# BoardB-FPGA2.net
KiCad netlist of a schematic drawn in Altium Designer
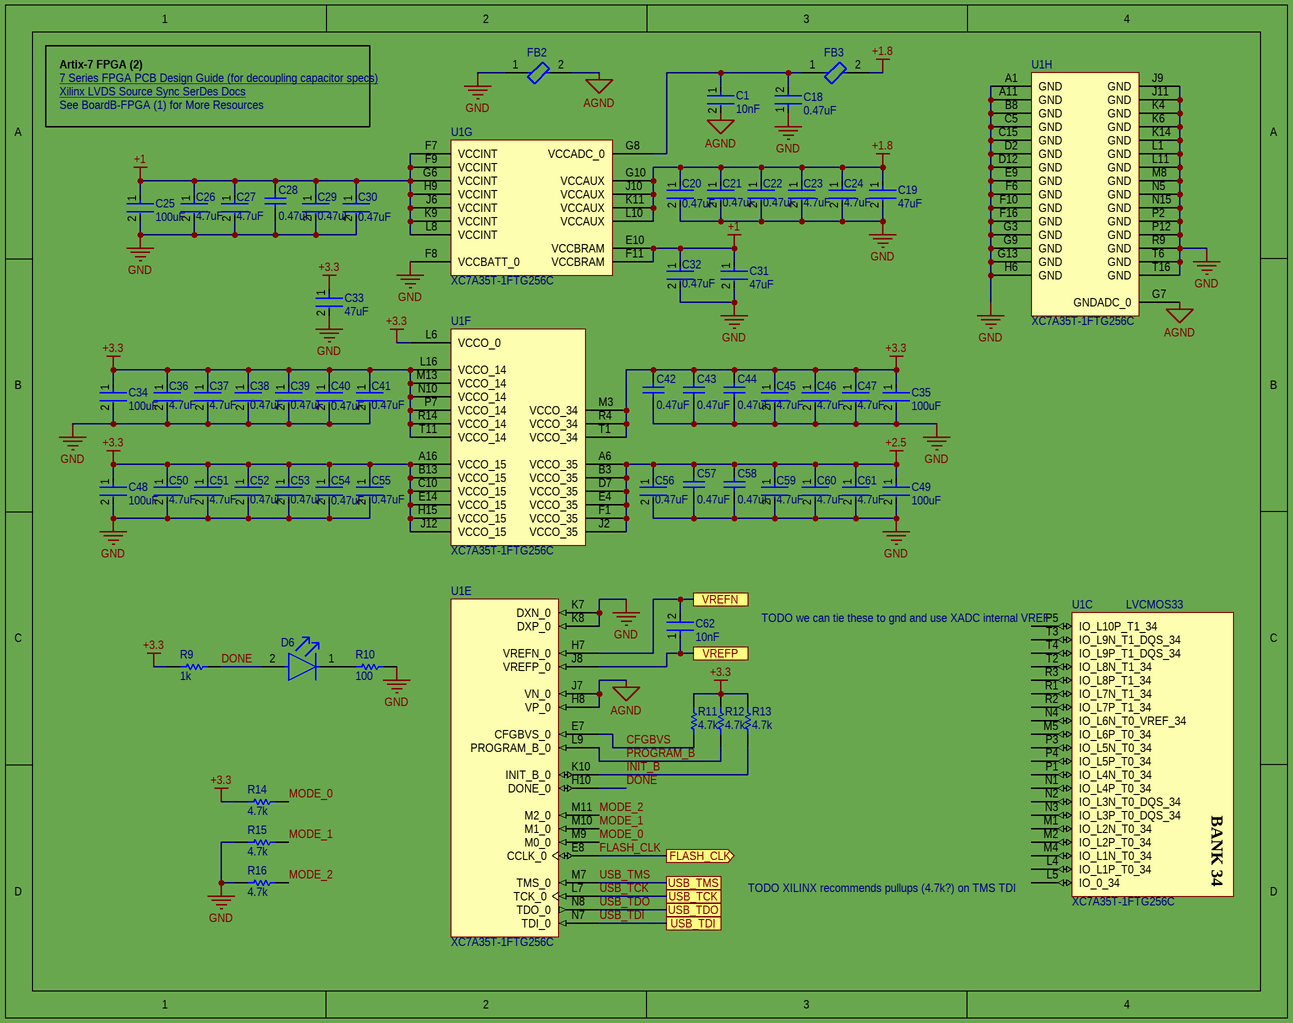
[diagram p0: BoardB-FPGA2.SchDoc]

(export (version "E")
  (design (tool "Eeschema 10.0.6"))
  (components
    (comp (ref "C1")
      (value "10nF")
      (footprint "FP-GRM033-0_03-IPC_C")
      (description "Chip Multilayer Ceramic Capacitors for General Purpose, 0201, 10000pF, X7R, 15%, 10%, 10V")
      (fields (field (name "VOLTAGE") "10V") (field (name "TOLERANCE") "10%"))
      (libsource (lib "Altium Content Vault") (part "b4654b650e69147ec39a6b967a45e02"))
    )
    (comp (ref "C18")
      (value "0.47uF")
      (footprint "FP-GRM033-0_03-IPC_C")
      (description "Chip Multilayer Ceramic Capacitors for General Purpose, 0201, 0.47uF, X5R, 15%, 10%, 6.3V")
      (fields (field (name "TOLERANCE") "10%"))
      (libsource (lib "Altium Content Vault") (part "b4654b650e69147ec39a6b967a45e02"))
    )
    (comp (ref "C19")
      (value "47uF")
      (footprint "FP-GRM188-0_2-MFG")
      (description "Chip Multilayer Ceramic Capacitors for General Purpose, 0603, 47uF, X5R, 15%, 20%, 6.3V")
      (fields (field (name "TOLERANCE") "20%"))
      (libsource (lib "Altium Content Vault") (part "11868f565c42a9108669ba33697ecf6"))
    )
    (comp (ref "C20")
      (value "0.47uF")
      (footprint "FP-GRM033-0_03-IPC_C")
      (description "Chip Multilayer Ceramic Capacitors for General Purpose, 0201, 0.47uF, X5R, 15%, 10%, 6.3V")
      (fields (field (name "TOLERANCE") "10%"))
      (libsource (lib "Altium Content Vault") (part "b4654b650e69147ec39a6b967a45e02"))
    )
    (comp (ref "C21")
      (value "0.47uF")
      (footprint "FP-GRM033-0_03-IPC_C")
      (description "Chip Multilayer Ceramic Capacitors for General Purpose, 0201, 0.47uF, X5R, 15%, 10%, 6.3V")
      (fields (field (name "TOLERANCE") "10%"))
      (libsource (lib "Altium Content Vault") (part "b4654b650e69147ec39a6b967a45e02"))
    )
    (comp (ref "C22")
      (value "0.47uF")
      (footprint "FP-GRM033-0_03-IPC_C")
      (description "Chip Multilayer Ceramic Capacitors for General Purpose, 0201, 0.47uF, X5R, 15%, 10%, 6.3V")
      (fields (field (name "TOLERANCE") "10%"))
      (libsource (lib "Altium Content Vault") (part "b4654b650e69147ec39a6b967a45e02"))
    )
    (comp (ref "C23")
      (value "4.7uF")
      (footprint "FP-GRM155-0_1-IPC_B")
      (description "Chip Multilayer Ceramic Capacitors for General Purpose, 0402, 4.7uF, X5R, 15%, 20%, 6.3V")
      (fields (field (name "VOLTAGE") "6.3V") (field (name "TOLERANCE") "20%"))
      (libsource (lib "Altium Content Vault") (part "11868f565c42a9108669ba33697ecf6"))
    )
    (comp (ref "C24")
      (value "4.7uF")
      (footprint "FP-GRM155-0_1-IPC_B")
      (description "Chip Multilayer Ceramic Capacitors for General Purpose, 0402, 4.7uF, X5R, 15%, 20%, 6.3V")
      (fields (field (name "VOLTAGE") "6.3V") (field (name "TOLERANCE") "20%"))
      (libsource (lib "Altium Content Vault") (part "11868f565c42a9108669ba33697ecf6"))
    )
    (comp (ref "C25")
      (value "100uF")
      (footprint "FP-GRM21B-0_2-e0_2_0_7-MFG")
      (description "Chip Multilayer Ceramic Capacitors for General Purpose, 0805, 100uF, X5R, 15%, 20%, 6.3V")
      (fields (field (name "TOLERANCE") "20%"))
      (libsource (lib "Altium Content Vault") (part "b4654b650e69147ec39a6b967a45e02"))
    )
    (comp (ref "C26")
      (value "4.7uF")
      (footprint "FP-GRM155-0_1-IPC_B")
      (description "Chip Multilayer Ceramic Capacitors for General Purpose, 0402, 4.7uF, X5R, 15%, 20%, 6.3V")
      (fields (field (name "VOLTAGE") "6.3V") (field (name "TOLERANCE") "20%"))
      (libsource (lib "Altium Content Vault") (part "11868f565c42a9108669ba33697ecf6"))
    )
    (comp (ref "C27")
      (value "4.7uF")
      (footprint "FP-GRM155-0_1-IPC_B")
      (description "Chip Multilayer Ceramic Capacitors for General Purpose, 0402, 4.7uF, X5R, 15%, 20%, 6.3V")
      (fields (field (name "VOLTAGE") "6.3V") (field (name "TOLERANCE") "20%"))
      (libsource (lib "Altium Content Vault") (part "11868f565c42a9108669ba33697ecf6"))
    )
    (comp (ref "C28")
      (value "0.47uF")
      (footprint "CAPC1005X55X25LL05T10")
      (fields (field (name "MANUFACTURER") "Murata") (field (name "PART NUMBER") "GRM155R60J474KE19D"))
      (libsource (lib "Altium Content Vault") (part "CAP"))
    )
    (comp (ref "C29")
      (value "0.47uF")
      (footprint "FP-GRM033-0_03-IPC_C")
      (description "Chip Multilayer Ceramic Capacitors for General Purpose, 0201, 0.47uF, X5R, 15%, 10%, 6.3V")
      (fields (field (name "TOLERANCE") "10%"))
      (libsource (lib "Altium Content Vault") (part "b4654b650e69147ec39a6b967a45e02"))
    )
    (comp (ref "C30")
      (value "0.47uF")
      (footprint "FP-GRM033-0_03-IPC_C")
      (description "Chip Multilayer Ceramic Capacitors for General Purpose, 0201, 0.47uF, X5R, 15%, 10%, 6.3V")
      (fields (field (name "TOLERANCE") "10%"))
      (libsource (lib "Altium Content Vault") (part "b4654b650e69147ec39a6b967a45e02"))
    )
    (comp (ref "C31")
      (value "47uF")
      (footprint "FP-GRM188-0_2-MFG")
      (description "Chip Multilayer Ceramic Capacitors for General Purpose, 0603, 47uF, X5R, 15%, 20%, 6.3V")
      (fields (field (name "TOLERANCE") "20%"))
      (libsource (lib "Altium Content Vault") (part "11868f565c42a9108669ba33697ecf6"))
    )
    (comp (ref "C32")
      (value "0.47uF")
      (footprint "FP-GRM033-0_03-IPC_C")
      (description "Chip Multilayer Ceramic Capacitors for General Purpose, 0201, 0.47uF, X5R, 15%, 10%, 6.3V")
      (fields (field (name "TOLERANCE") "10%"))
      (libsource (lib "Altium Content Vault") (part "b4654b650e69147ec39a6b967a45e02"))
    )
    (comp (ref "C33")
      (value "47uF")
      (footprint "FP-GRM188-0_2-MFG")
      (description "Chip Multilayer Ceramic Capacitors for General Purpose, 0603, 47uF, X5R, 15%, 20%, 6.3V")
      (fields (field (name "TOLERANCE") "20%"))
      (libsource (lib "Altium Content Vault") (part "11868f565c42a9108669ba33697ecf6"))
    )
    (comp (ref "C34")
      (value "100uF")
      (footprint "FP-GRM21B-0_2-e0_2_0_7-MFG")
      (description "Chip Multilayer Ceramic Capacitors for General Purpose, 0805, 100uF, X5R, 15%, 20%, 6.3V")
      (fields (field (name "TOLERANCE") "20%"))
      (libsource (lib "Altium Content Vault") (part "b4654b650e69147ec39a6b967a45e02"))
    )
    (comp (ref "C35")
      (value "100uF")
      (footprint "FP-GRM21B-0_2-e0_2_0_7-MFG")
      (description "Chip Multilayer Ceramic Capacitors for General Purpose, 0805, 100uF, X5R, 15%, 20%, 6.3V")
      (fields (field (name "TOLERANCE") "20%"))
      (libsource (lib "Altium Content Vault") (part "b4654b650e69147ec39a6b967a45e02"))
    )
    (comp (ref "C36")
      (value "4.7uF")
      (footprint "FP-GRM155-0_1-IPC_B")
      (description "Chip Multilayer Ceramic Capacitors for General Purpose, 0402, 4.7uF, X5R, 15%, 20%, 6.3V")
      (fields (field (name "VOLTAGE") "6.3V") (field (name "TOLERANCE") "20%"))
      (libsource (lib "Altium Content Vault") (part "11868f565c42a9108669ba33697ecf6"))
    )
    (comp (ref "C37")
      (value "4.7uF")
      (footprint "FP-GRM155-0_1-IPC_B")
      (description "Chip Multilayer Ceramic Capacitors for General Purpose, 0402, 4.7uF, X5R, 15%, 20%, 6.3V")
      (fields (field (name "VOLTAGE") "6.3V") (field (name "TOLERANCE") "20%"))
      (libsource (lib "Altium Content Vault") (part "11868f565c42a9108669ba33697ecf6"))
    )
    (comp (ref "C38")
      (value "0.47uF")
      (footprint "FP-GRM033-0_03-IPC_C")
      (description "Chip Multilayer Ceramic Capacitors for General Purpose, 0201, 0.47uF, X5R, 15%, 10%, 6.3V")
      (fields (field (name "TOLERANCE") "10%"))
      (libsource (lib "Altium Content Vault") (part "b4654b650e69147ec39a6b967a45e02"))
    )
    (comp (ref "C39")
      (value "0.47uF")
      (footprint "FP-GRM033-0_03-IPC_C")
      (description "Chip Multilayer Ceramic Capacitors for General Purpose, 0201, 0.47uF, X5R, 15%, 10%, 6.3V")
      (fields (field (name "TOLERANCE") "10%"))
      (libsource (lib "Altium Content Vault") (part "b4654b650e69147ec39a6b967a45e02"))
    )
    (comp (ref "C40")
      (value "0.47uF")
      (footprint "FP-GRM033-0_03-IPC_C")
      (description "Chip Multilayer Ceramic Capacitors for General Purpose, 0201, 0.47uF, X5R, 15%, 10%, 6.3V")
      (fields (field (name "TOLERANCE") "10%"))
      (libsource (lib "Altium Content Vault") (part "b4654b650e69147ec39a6b967a45e02"))
    )
    (comp (ref "C41")
      (value "0.47uF")
      (footprint "FP-GRM033-0_03-IPC_C")
      (description "Chip Multilayer Ceramic Capacitors for General Purpose, 0201, 0.47uF, X5R, 15%, 10%, 6.3V")
      (fields (field (name "TOLERANCE") "10%"))
      (libsource (lib "Altium Content Vault") (part "b4654b650e69147ec39a6b967a45e02"))
    )
    (comp (ref "C42")
      (value "0.47uF")
      (footprint "CAPC1005X55X25LL05T10")
      (fields (field (name "MANUFACTURER") "Murata") (field (name "PART NUMBER") "GRM155R60J474KE19D"))
      (libsource (lib "Altium Content Vault") (part "CAP"))
    )
    (comp (ref "C43")
      (value "0.47uF")
      (footprint "CAPC1005X55X25LL05T10")
      (fields (field (name "MANUFACTURER") "Murata") (field (name "PART NUMBER") "GRM155R60J474KE19D"))
      (libsource (lib "Altium Content Vault") (part "CAP"))
    )
    (comp (ref "C44")
      (value "0.47uF")
      (footprint "CAPC1005X55X25LL05T10")
      (fields (field (name "MANUFACTURER") "Murata") (field (name "PART NUMBER") "GRM155R60J474KE19D"))
      (libsource (lib "Altium Content Vault") (part "CAP"))
    )
    (comp (ref "C45")
      (value "4.7uF")
      (footprint "FP-GRM155-0_1-IPC_B")
      (description "Chip Multilayer Ceramic Capacitors for General Purpose, 0402, 4.7uF, X5R, 15%, 20%, 6.3V")
      (fields (field (name "VOLTAGE") "6.3V") (field (name "TOLERANCE") "20%"))
      (libsource (lib "Altium Content Vault") (part "11868f565c42a9108669ba33697ecf6"))
    )
    (comp (ref "C46")
      (value "4.7uF")
      (footprint "FP-GRM155-0_1-IPC_B")
      (description "Chip Multilayer Ceramic Capacitors for General Purpose, 0402, 4.7uF, X5R, 15%, 20%, 6.3V")
      (fields (field (name "VOLTAGE") "6.3V") (field (name "TOLERANCE") "20%"))
      (libsource (lib "Altium Content Vault") (part "11868f565c42a9108669ba33697ecf6"))
    )
    (comp (ref "C47")
      (value "4.7uF")
      (footprint "FP-GRM155-0_1-IPC_B")
      (description "Chip Multilayer Ceramic Capacitors for General Purpose, 0402, 4.7uF, X5R, 15%, 20%, 6.3V")
      (fields (field (name "VOLTAGE") "6.3V") (field (name "TOLERANCE") "20%"))
      (libsource (lib "Altium Content Vault") (part "11868f565c42a9108669ba33697ecf6"))
    )
    (comp (ref "C48")
      (value "100uF")
      (footprint "FP-GRM21B-0_2-e0_2_0_7-MFG")
      (description "Chip Multilayer Ceramic Capacitors for General Purpose, 0805, 100uF, X5R, 15%, 20%, 6.3V")
      (fields (field (name "TOLERANCE") "20%"))
      (libsource (lib "Altium Content Vault") (part "b4654b650e69147ec39a6b967a45e02"))
    )
    (comp (ref "C49")
      (value "100uF")
      (footprint "FP-GRM21B-0_2-e0_2_0_7-MFG")
      (description "Chip Multilayer Ceramic Capacitors for General Purpose, 0805, 100uF, X5R, 15%, 20%, 6.3V")
      (fields (field (name "TOLERANCE") "20%"))
      (libsource (lib "Altium Content Vault") (part "b4654b650e69147ec39a6b967a45e02"))
    )
    (comp (ref "C50")
      (value "4.7uF")
      (footprint "FP-GRM155-0_1-IPC_B")
      (description "Chip Multilayer Ceramic Capacitors for General Purpose, 0402, 4.7uF, X5R, 15%, 20%, 6.3V")
      (fields (field (name "VOLTAGE") "6.3V") (field (name "TOLERANCE") "20%"))
      (libsource (lib "Altium Content Vault") (part "11868f565c42a9108669ba33697ecf6"))
    )
    (comp (ref "C51")
      (value "4.7uF")
      (footprint "FP-GRM155-0_1-IPC_B")
      (description "Chip Multilayer Ceramic Capacitors for General Purpose, 0402, 4.7uF, X5R, 15%, 20%, 6.3V")
      (fields (field (name "VOLTAGE") "6.3V") (field (name "TOLERANCE") "20%"))
      (libsource (lib "Altium Content Vault") (part "11868f565c42a9108669ba33697ecf6"))
    )
    (comp (ref "C52")
      (value "0.47uF")
      (footprint "FP-GRM033-0_03-IPC_C")
      (description "Chip Multilayer Ceramic Capacitors for General Purpose, 0201, 0.47uF, X5R, 15%, 10%, 6.3V")
      (fields (field (name "TOLERANCE") "10%"))
      (libsource (lib "Altium Content Vault") (part "b4654b650e69147ec39a6b967a45e02"))
    )
    (comp (ref "C53")
      (value "0.47uF")
      (footprint "FP-GRM033-0_03-IPC_C")
      (description "Chip Multilayer Ceramic Capacitors for General Purpose, 0201, 0.47uF, X5R, 15%, 10%, 6.3V")
      (fields (field (name "TOLERANCE") "10%"))
      (libsource (lib "Altium Content Vault") (part "b4654b650e69147ec39a6b967a45e02"))
    )
    (comp (ref "C54")
      (value "0.47uF")
      (footprint "FP-GRM033-0_03-IPC_C")
      (description "Chip Multilayer Ceramic Capacitors for General Purpose, 0201, 0.47uF, X5R, 15%, 10%, 6.3V")
      (fields (field (name "TOLERANCE") "10%"))
      (libsource (lib "Altium Content Vault") (part "b4654b650e69147ec39a6b967a45e02"))
    )
    (comp (ref "C55")
      (value "0.47uF")
      (footprint "FP-GRM033-0_03-IPC_C")
      (description "Chip Multilayer Ceramic Capacitors for General Purpose, 0201, 0.47uF, X5R, 15%, 10%, 6.3V")
      (fields (field (name "TOLERANCE") "10%"))
      (libsource (lib "Altium Content Vault") (part "b4654b650e69147ec39a6b967a45e02"))
    )
    (comp (ref "C56")
      (value "0.47uF")
      (footprint "FP-GRM033-0_03-IPC_C")
      (description "Chip Multilayer Ceramic Capacitors for General Purpose, 0201, 0.47uF, X5R, 15%, 10%, 6.3V")
      (fields (field (name "TOLERANCE") "10%"))
      (libsource (lib "Altium Content Vault") (part "b4654b650e69147ec39a6b967a45e02"))
    )
    (comp (ref "C57")
      (value "0.47uF")
      (footprint "CAPC1005X55X25LL05T10")
      (fields (field (name "MANUFACTURER") "Murata") (field (name "PART NUMBER") "GRM155R60J474KE19D"))
      (libsource (lib "Altium Content Vault") (part "CAP"))
    )
    (comp (ref "C58")
      (value "0.47uF")
      (footprint "CAPC1005X55X25LL05T10")
      (fields (field (name "MANUFACTURER") "Murata") (field (name "PART NUMBER") "GRM155R60J474KE19D"))
      (libsource (lib "Altium Content Vault") (part "CAP"))
    )
    (comp (ref "C59")
      (value "4.7uF")
      (footprint "FP-GRM155-0_1-IPC_B")
      (description "Chip Multilayer Ceramic Capacitors for General Purpose, 0402, 4.7uF, X5R, 15%, 20%, 6.3V")
      (fields (field (name "VOLTAGE") "6.3V") (field (name "TOLERANCE") "20%"))
      (libsource (lib "Altium Content Vault") (part "11868f565c42a9108669ba33697ecf6"))
    )
    (comp (ref "C60")
      (value "4.7uF")
      (footprint "FP-GRM155-0_1-IPC_B")
      (description "Chip Multilayer Ceramic Capacitors for General Purpose, 0402, 4.7uF, X5R, 15%, 20%, 6.3V")
      (fields (field (name "VOLTAGE") "6.3V") (field (name "TOLERANCE") "20%"))
      (libsource (lib "Altium Content Vault") (part "11868f565c42a9108669ba33697ecf6"))
    )
    (comp (ref "C61")
      (value "4.7uF")
      (footprint "FP-GRM155-0_1-IPC_B")
      (description "Chip Multilayer Ceramic Capacitors for General Purpose, 0402, 4.7uF, X5R, 15%, 20%, 6.3V")
      (fields (field (name "VOLTAGE") "6.3V") (field (name "TOLERANCE") "20%"))
      (libsource (lib "Altium Content Vault") (part "11868f565c42a9108669ba33697ecf6"))
    )
    (comp (ref "C62")
      (value "10nF")
      (footprint "FP-CC0201-BA-MFG")
      (description "CAP CER 10000PF 16V X7R 0201")
      (fields
        (field (name "OCTOPART") "https://octopart.com/cc0201krx7r7bb103-yageo-9292627")
        (field (name "MANUFACTURER") "Yageo")
      )
      (libsource (lib "Altium Content Vault") (part "11868f565c42a9108669ba33697ecf6"))
    )
    (comp (ref "D6")
      (value "SML-D12U1WT86")
      (footprint "FP-SML-D12-MFG")
      (description "LED RED DIFFUSED 1608 SMD")
      (fields
        (field (name "MANUFACTURER") "Rohm")
        (field (name "OCTOPART") "https://octopart.com/sml-d12u1wt86-rohm-70850259")
      )
      (libsource (lib "Altium Content Vault") (part "8706943c75ba83719d021d2fdc84c58"))
    )
    (comp (ref "FB2")
      (value "BLM18AG601SN1D")
      (footprint "FP-BLM18-0_15-t0_8-MFG")
      (description "Chip Ferrite Bead, 0603, 600Ω @ 100MHz, 0.38Ω, 25%, 500mA")
      (fields (field (name "TOLERANCE") "25%"))
      (libsource (lib "Altium Content Vault") (part "5f30dd21d616792df468990f7003faa"))
    )
    (comp (ref "FB3")
      (value "BLM18AG601SN1D")
      (footprint "FP-BLM18-0_15-t0_8-MFG")
      (description "Chip Ferrite Bead, 0603, 600Ω @ 100MHz, 0.38Ω, 25%, 500mA")
      (fields (field (name "TOLERANCE") "25%"))
      (libsource (lib "Altium Content Vault") (part "5f30dd21d616792df468990f7003faa"))
    )
    (comp (ref "R9")
      (value "1k")
      (footprint "RESC1005X40X25NL05T05")
      (description "Chip Resistor, 1 KOhm, +/- 1%, 100 mW, -55 to 155 degC, 0402 (1005 Metric), RoHS, Tape and Reel")
      (fields (field (name "PARTNUMBER") "ERJ-2RKF1001X") (field (name "MANUFACTURER") "Basic Passives"))
      (libsource (lib "Altium Content Vault") (part "RES-2"))
    )
    (comp (ref "R10")
      (value "100")
      (footprint "RESC1005X40X25LL05T05")
      (description "Chip Resistor, 100 Ohm, +/- 1%, 100 mW, -55 to 155 degC, 0402 (1005 Metric), RoHS, Tape and Reel")
      (fields (field (name "MANUFACTURER") "Basic Passives") (field (name "TOLERANCE") "1%"))
      (libsource (lib "Altium Content Vault") (part "RES-2"))
    )
    (comp (ref "R11")
      (value "4.7k")
      (footprint "RESC1005X40X25LL05T05")
      (description "Chip Resistor, 4.7 KOhm, +/- 1%, 0.1 W, -55 to 155 degC, 0402 (1005 Metric), RoHS, Tape and Reel")
      (fields (field (name "TOLERANCE") "1%") (field (name "PARTNUMBER") "ERJ-2RKF4701X"))
      (libsource (lib "Altium Content Vault") (part "RES-2"))
    )
    (comp (ref "R12")
      (value "4.7k")
      (footprint "RESC1005X40X25LL05T05")
      (description "Chip Resistor, 4.7 KOhm, +/- 1%, 0.1 W, -55 to 155 degC, 0402 (1005 Metric), RoHS, Tape and Reel")
      (fields (field (name "TOLERANCE") "1%") (field (name "PARTNUMBER") "ERJ-2RKF4701X"))
      (libsource (lib "Altium Content Vault") (part "RES-2"))
    )
    (comp (ref "R13")
      (value "4.7k")
      (footprint "RESC1005X40X25LL05T05")
      (description "Chip Resistor, 4.7 KOhm, +/- 1%, 0.1 W, -55 to 155 degC, 0402 (1005 Metric), RoHS, Tape and Reel")
      (fields (field (name "TOLERANCE") "1%") (field (name "PARTNUMBER") "ERJ-2RKF4701X"))
      (libsource (lib "Altium Content Vault") (part "RES-2"))
    )
    (comp (ref "R14")
      (value "4.7k")
      (footprint "RESC1005X40X25LL05T05")
      (description "Chip Resistor, 4.7 KOhm, +/- 1%, 0.1 W, -55 to 155 degC, 0402 (1005 Metric), RoHS, Tape and Reel")
      (fields (field (name "TOLERANCE") "1%") (field (name "PARTNUMBER") "ERJ-2RKF4701X"))
      (libsource (lib "Altium Content Vault") (part "RES-2"))
    )
    (comp (ref "R15")
      (value "4.7k")
      (footprint "RESC1005X40X25LL05T05")
      (description "Chip Resistor, 4.7 KOhm, +/- 1%, 0.1 W, -55 to 155 degC, 0402 (1005 Metric), RoHS, Tape and Reel")
      (fields (field (name "TOLERANCE") "1%") (field (name "PARTNUMBER") "ERJ-2RKF4701X"))
      (libsource (lib "Altium Content Vault") (part "RES-2"))
    )
    (comp (ref "R16")
      (value "4.7k")
      (footprint "RESC1005X40X25LL05T05")
      (description "Chip Resistor, 4.7 KOhm, +/- 1%, 0.1 W, -55 to 155 degC, 0402 (1005 Metric), RoHS, Tape and Reel")
      (fields (field (name "TOLERANCE") "1%") (field (name "PARTNUMBER") "ERJ-2RKF4701X"))
      (libsource (lib "Altium Content Vault") (part "RES-2"))
    )
    (comp (ref "U1")
      (value "XC7A35T-1FTG256C")
      (footprint "FTG256")
      (description "Artix-7 FPGA, 170 User I/Os, 0 GTP, 256-Ball BGA, Speed Grade 1, Commercial Grade, Pb-Free")
      (fields (field (name "MANUFACTURER") "Xilinx"))
      (libsource (lib "Altium Content Vault") (part "XLNX-XC7A35T-FTG256"))
    )
  )
  (nets
    (net (code "1") (name "+1") (class "Default")
      (node (ref "C25") (pin "1") (pinfunction "1_1") (pintype "passive"))
      (node (ref "C26") (pin "1") (pinfunction "1_1") (pintype "passive"))
      (node (ref "C27") (pin "1") (pinfunction "1_1") (pintype "passive"))
      (node (ref "C28") (pin "2") (pinfunction "2_2") (pintype "passive"))
      (node (ref "C29") (pin "1") (pinfunction "1_1") (pintype "passive"))
      (node (ref "C30") (pin "1") (pinfunction "1_1") (pintype "passive"))
      (node (ref "C31") (pin "1") (pinfunction "1_1") (pintype "passive"))
      (node (ref "C32") (pin "1") (pinfunction "1_1") (pintype "passive"))
      (node (ref "U1") (pin "E10") (pinfunction "VCCBRAM_E10") (pintype "power_in"))
      (node (ref "U1") (pin "F11") (pinfunction "VCCBRAM_F11") (pintype "power_in"))
      (node (ref "U1") (pin "F7") (pinfunction "VCCINT_F7") (pintype "power_in"))
      (node (ref "U1") (pin "F9") (pinfunction "VCCINT_F9") (pintype "power_in"))
      (node (ref "U1") (pin "G6") (pinfunction "VCCINT_G6") (pintype "power_in"))
      (node (ref "U1") (pin "H9") (pinfunction "VCCINT_H9") (pintype "power_in"))
      (node (ref "U1") (pin "J6") (pinfunction "VCCINT_J6") (pintype "power_in"))
      (node (ref "U1") (pin "K9") (pinfunction "VCCINT_K9") (pintype "power_in"))
      (node (ref "U1") (pin "L8") (pinfunction "VCCINT_L8") (pintype "power_in"))
    )
    (net (code "2") (name "+1.8") (class "Default")
      (node (ref "C19") (pin "1") (pinfunction "1_1") (pintype "passive"))
      (node (ref "C20") (pin "1") (pinfunction "1_1") (pintype "passive"))
      (node (ref "C21") (pin "1") (pinfunction "1_1") (pintype "passive"))
      (node (ref "C22") (pin "1") (pinfunction "1_1") (pintype "passive"))
      (node (ref "C23") (pin "1") (pinfunction "1_1") (pintype "passive"))
      (node (ref "C24") (pin "1") (pinfunction "1_1") (pintype "passive"))
      (node (ref "FB3") (pin "2") (pinfunction "2_2") (pintype "passive"))
      (node (ref "U1") (pin "G10") (pinfunction "VCCAUX_G10") (pintype "power_in"))
      (node (ref "U1") (pin "J10") (pinfunction "VCCAUX_J10") (pintype "power_in"))
      (node (ref "U1") (pin "K11") (pinfunction "VCCAUX_K11") (pintype "power_in"))
      (node (ref "U1") (pin "L10") (pinfunction "VCCAUX_L10") (pintype "power_in"))
    )
    (net (code "3") (name "+2.5") (class "Default")
      (node (ref "C49") (pin "1") (pinfunction "1_1") (pintype "passive"))
      (node (ref "C56") (pin "1") (pinfunction "1_1") (pintype "passive"))
      (node (ref "C57") (pin "2") (pinfunction "2_2") (pintype "passive"))
      (node (ref "C58") (pin "2") (pinfunction "2_2") (pintype "passive"))
      (node (ref "C59") (pin "1") (pinfunction "1_1") (pintype "passive"))
      (node (ref "C60") (pin "1") (pinfunction "1_1") (pintype "passive"))
      (node (ref "C61") (pin "1") (pinfunction "1_1") (pintype "passive"))
      (node (ref "U1") (pin "A6") (pinfunction "VCCO_35_A6") (pintype "power_in"))
      (node (ref "U1") (pin "B3") (pinfunction "VCCO_35_B3") (pintype "power_in"))
      (node (ref "U1") (pin "D7") (pinfunction "VCCO_35_D7") (pintype "power_in"))
      (node (ref "U1") (pin "E4") (pinfunction "VCCO_35_E4") (pintype "power_in"))
      (node (ref "U1") (pin "F1") (pinfunction "VCCO_35_F1") (pintype "power_in"))
      (node (ref "U1") (pin "J2") (pinfunction "VCCO_35_J2") (pintype "power_in"))
    )
    (net (code "4") (name "+3.3") (class "Default")
      (node (ref "C33") (pin "1") (pinfunction "1_1") (pintype "passive"))
      (node (ref "C34") (pin "1") (pinfunction "1_1") (pintype "passive"))
      (node (ref "C35") (pin "1") (pinfunction "1_1") (pintype "passive"))
      (node (ref "C36") (pin "1") (pinfunction "1_1") (pintype "passive"))
      (node (ref "C37") (pin "1") (pinfunction "1_1") (pintype "passive"))
      (node (ref "C38") (pin "1") (pinfunction "1_1") (pintype "passive"))
      (node (ref "C39") (pin "1") (pinfunction "1_1") (pintype "passive"))
      (node (ref "C40") (pin "1") (pinfunction "1_1") (pintype "passive"))
      (node (ref "C41") (pin "1") (pinfunction "1_1") (pintype "passive"))
      (node (ref "C42") (pin "2") (pinfunction "2_2") (pintype "passive"))
      (node (ref "C43") (pin "2") (pinfunction "2_2") (pintype "passive"))
      (node (ref "C44") (pin "2") (pinfunction "2_2") (pintype "passive"))
      (node (ref "C45") (pin "1") (pinfunction "1_1") (pintype "passive"))
      (node (ref "C46") (pin "1") (pinfunction "1_1") (pintype "passive"))
      (node (ref "C47") (pin "1") (pinfunction "1_1") (pintype "passive"))
      (node (ref "C48") (pin "1") (pinfunction "1_1") (pintype "passive"))
      (node (ref "C50") (pin "1") (pinfunction "1_1") (pintype "passive"))
      (node (ref "C51") (pin "1") (pinfunction "1_1") (pintype "passive"))
      (node (ref "C52") (pin "1") (pinfunction "1_1") (pintype "passive"))
      (node (ref "C53") (pin "1") (pinfunction "1_1") (pintype "passive"))
      (node (ref "C54") (pin "1") (pinfunction "1_1") (pintype "passive"))
      (node (ref "C55") (pin "1") (pinfunction "1_1") (pintype "passive"))
      (node (ref "R11") (pin "2") (pinfunction "2_2") (pintype "passive"))
      (node (ref "R12") (pin "2") (pinfunction "2_2") (pintype "passive"))
      (node (ref "R13") (pin "2") (pinfunction "2_2") (pintype "passive"))
      (node (ref "R14") (pin "1") (pinfunction "1_1") (pintype "passive"))
      (node (ref "R9") (pin "1") (pinfunction "1_1") (pintype "passive"))
      (node (ref "U1") (pin "A16") (pinfunction "VCCO_15_A16") (pintype "power_in"))
      (node (ref "U1") (pin "B13") (pinfunction "VCCO_15_B13") (pintype "power_in"))
      (node (ref "U1") (pin "C10") (pinfunction "VCCO_15_C10") (pintype "power_in"))
      (node (ref "U1") (pin "E14") (pinfunction "VCCO_15_E14") (pintype "power_in"))
      (node (ref "U1") (pin "H15") (pinfunction "VCCO_15_H15") (pintype "power_in"))
      (node (ref "U1") (pin "J12") (pinfunction "VCCO_15_J12") (pintype "power_in"))
      (node (ref "U1") (pin "L16") (pinfunction "VCCO_14_L16") (pintype "power_in"))
      (node (ref "U1") (pin "L6") (pinfunction "VCCO_0_L6") (pintype "power_in"))
      (node (ref "U1") (pin "M13") (pinfunction "VCCO_14_M13") (pintype "power_in"))
      (node (ref "U1") (pin "M3") (pinfunction "VCCO_34_M3") (pintype "power_in"))
      (node (ref "U1") (pin "N10") (pinfunction "VCCO_14_N10") (pintype "power_in"))
      (node (ref "U1") (pin "P7") (pinfunction "VCCO_14_P7") (pintype "power_in"))
      (node (ref "U1") (pin "R14") (pinfunction "VCCO_14_R14") (pintype "power_in"))
      (node (ref "U1") (pin "R4") (pinfunction "VCCO_34_R4") (pintype "power_in"))
      (node (ref "U1") (pin "T1") (pinfunction "VCCO_34_T1") (pintype "power_in"))
      (node (ref "U1") (pin "T11") (pinfunction "VCCO_14_T11") (pintype "power_in"))
    )
    (net (code "5") (name "/CFGBVS") (class "Default")
      (node (ref "R11") (pin "1") (pinfunction "1_1") (pintype "passive"))
      (node (ref "U1") (pin "E7") (pinfunction "CFGBVS_0_E7") (pintype "input"))
    )
    (net (code "6") (name "/DONE") (class "Default")
      (node (ref "D6") (pin "2") (pinfunction "A_2") (pintype "passive"))
      (node (ref "R9") (pin "2") (pinfunction "2_2") (pintype "passive"))
      (node (ref "U1") (pin "H10") (pinfunction "DONE_0_H10") (pintype "bidirectional"))
    )
    (net (code "7") (name "/FLASH_CLK") (class "Default")
      (node (ref "U1") (pin "E8") (pinfunction "CCLK_0_E8") (pintype "bidirectional"))
    )
    (net (code "8") (name "/INIT_B") (class "Default")
      (node (ref "R13") (pin "1") (pinfunction "1_1") (pintype "passive"))
      (node (ref "U1") (pin "K10") (pinfunction "INIT_B_0_K10") (pintype "bidirectional"))
    )
    (net (code "9") (name "/MODE_0") (class "Default")
      (node (ref "R14") (pin "2") (pinfunction "2_2") (pintype "passive"))
      (node (ref "U1") (pin "M9") (pinfunction "M0_0_M9") (pintype "input"))
    )
    (net (code "10") (name "/MODE_1") (class "Default")
      (node (ref "R15") (pin "2") (pinfunction "2_2") (pintype "passive"))
      (node (ref "U1") (pin "M10") (pinfunction "M1_0_M10") (pintype "input"))
    )
    (net (code "11") (name "/MODE_2") (class "Default")
      (node (ref "R16") (pin "2") (pinfunction "2_2") (pintype "passive"))
      (node (ref "U1") (pin "M11") (pinfunction "M2_0_M11") (pintype "input"))
    )
    (net (code "12") (name "/PROGRAM_B") (class "Default")
      (node (ref "R12") (pin "1") (pinfunction "1_1") (pintype "passive"))
      (node (ref "U1") (pin "L9") (pinfunction "PROGRAM_B_0_L9") (pintype "input"))
    )
    (net (code "13") (name "/USB_TCK") (class "Default")
      (node (ref "U1") (pin "L7") (pinfunction "TCK_0_L7") (pintype "input"))
    )
    (net (code "14") (name "/USB_TDI") (class "Default")
      (node (ref "U1") (pin "N7") (pinfunction "TDI_0_N7") (pintype "input"))
    )
    (net (code "15") (name "/USB_TDO") (class "Default")
      (node (ref "U1") (pin "N8") (pinfunction "TDO_0_N8") (pintype "output"))
    )
    (net (code "16") (name "/USB_TMS") (class "Default")
      (node (ref "U1") (pin "M7") (pinfunction "TMS_0_M7") (pintype "input"))
    )
    (net (code "17") (name "/VREFN") (class "Default")
      (node (ref "C62") (pin "2") (pinfunction "2_2") (pintype "passive"))
      (node (ref "U1") (pin "H7") (pinfunction "VREFN_0_H7") (pintype "input"))
    )
    (net (code "18") (name "/VREFP") (class "Default")
      (node (ref "C62") (pin "1") (pinfunction "1_1") (pintype "passive"))
      (node (ref "U1") (pin "J8") (pinfunction "VREFP_0_J8") (pintype "input"))
    )
    (net (code "19") (name "AGND") (class "Default")
      (node (ref "C1") (pin "2") (pinfunction "2_2") (pintype "passive"))
      (node (ref "FB2") (pin "2") (pinfunction "2_2") (pintype "passive"))
      (node (ref "U1") (pin "G7") (pinfunction "GNDADC_0_G7") (pintype "power_in"))
      (node (ref "U1") (pin "H8") (pinfunction "VP_0_H8") (pintype "input"))
      (node (ref "U1") (pin "J7") (pinfunction "VN_0_J7") (pintype "input"))
    )
    (net (code "20") (name "GND") (class "Default")
      (node (ref "C18") (pin "1") (pinfunction "1_1") (pintype "passive"))
      (node (ref "C19") (pin "2") (pinfunction "2_2") (pintype "passive"))
      (node (ref "C20") (pin "2") (pinfunction "2_2") (pintype "passive"))
      (node (ref "C21") (pin "2") (pinfunction "2_2") (pintype "passive"))
      (node (ref "C22") (pin "2") (pinfunction "2_2") (pintype "passive"))
      (node (ref "C23") (pin "2") (pinfunction "2_2") (pintype "passive"))
      (node (ref "C24") (pin "2") (pinfunction "2_2") (pintype "passive"))
      (node (ref "C25") (pin "2") (pinfunction "2_2") (pintype "passive"))
      (node (ref "C26") (pin "2") (pinfunction "2_2") (pintype "passive"))
      (node (ref "C27") (pin "2") (pinfunction "2_2") (pintype "passive"))
      (node (ref "C28") (pin "1") (pinfunction "1_1") (pintype "passive"))
      (node (ref "C29") (pin "2") (pinfunction "2_2") (pintype "passive"))
      (node (ref "C30") (pin "2") (pinfunction "2_2") (pintype "passive"))
      (node (ref "C31") (pin "2") (pinfunction "2_2") (pintype "passive"))
      (node (ref "C32") (pin "2") (pinfunction "2_2") (pintype "passive"))
      (node (ref "C33") (pin "2") (pinfunction "2_2") (pintype "passive"))
      (node (ref "C34") (pin "2") (pinfunction "2_2") (pintype "passive"))
      (node (ref "C35") (pin "2") (pinfunction "2_2") (pintype "passive"))
      (node (ref "C36") (pin "2") (pinfunction "2_2") (pintype "passive"))
      (node (ref "C37") (pin "2") (pinfunction "2_2") (pintype "passive"))
      (node (ref "C38") (pin "2") (pinfunction "2_2") (pintype "passive"))
      (node (ref "C39") (pin "2") (pinfunction "2_2") (pintype "passive"))
      (node (ref "C40") (pin "2") (pinfunction "2_2") (pintype "passive"))
      (node (ref "C41") (pin "2") (pinfunction "2_2") (pintype "passive"))
      (node (ref "C42") (pin "1") (pinfunction "1_1") (pintype "passive"))
      (node (ref "C43") (pin "1") (pinfunction "1_1") (pintype "passive"))
      (node (ref "C44") (pin "1") (pinfunction "1_1") (pintype "passive"))
      (node (ref "C45") (pin "2") (pinfunction "2_2") (pintype "passive"))
      (node (ref "C46") (pin "2") (pinfunction "2_2") (pintype "passive"))
      (node (ref "C47") (pin "2") (pinfunction "2_2") (pintype "passive"))
      (node (ref "C48") (pin "2") (pinfunction "2_2") (pintype "passive"))
      (node (ref "C49") (pin "2") (pinfunction "2_2") (pintype "passive"))
      (node (ref "C50") (pin "2") (pinfunction "2_2") (pintype "passive"))
      (node (ref "C51") (pin "2") (pinfunction "2_2") (pintype "passive"))
      (node (ref "C52") (pin "2") (pinfunction "2_2") (pintype "passive"))
      (node (ref "C53") (pin "2") (pinfunction "2_2") (pintype "passive"))
      (node (ref "C54") (pin "2") (pinfunction "2_2") (pintype "passive"))
      (node (ref "C55") (pin "2") (pinfunction "2_2") (pintype "passive"))
      (node (ref "C56") (pin "2") (pinfunction "2_2") (pintype "passive"))
      (node (ref "C57") (pin "1") (pinfunction "1_1") (pintype "passive"))
      (node (ref "C58") (pin "1") (pinfunction "1_1") (pintype "passive"))
      (node (ref "C59") (pin "2") (pinfunction "2_2") (pintype "passive"))
      (node (ref "C60") (pin "2") (pinfunction "2_2") (pintype "passive"))
      (node (ref "C61") (pin "2") (pinfunction "2_2") (pintype "passive"))
      (node (ref "FB2") (pin "1") (pinfunction "1_1") (pintype "passive"))
      (node (ref "R10") (pin "2") (pinfunction "2_2") (pintype "passive"))
      (node (ref "R15") (pin "1") (pinfunction "1_1") (pintype "passive"))
      (node (ref "R16") (pin "1") (pinfunction "1_1") (pintype "passive"))
      (node (ref "U1") (pin "A1") (pinfunction "GND_A1") (pintype "power_in"))
      (node (ref "U1") (pin "A11") (pinfunction "GND_A11") (pintype "power_in"))
      (node (ref "U1") (pin "B8") (pinfunction "GND_B8") (pintype "power_in"))
      (node (ref "U1") (pin "C15") (pinfunction "GND_C15") (pintype "power_in"))
      (node (ref "U1") (pin "C5") (pinfunction "GND_C5") (pintype "power_in"))
      (node (ref "U1") (pin "D12") (pinfunction "GND_D12") (pintype "power_in"))
      (node (ref "U1") (pin "D2") (pinfunction "GND_D2") (pintype "power_in"))
      (node (ref "U1") (pin "E9") (pinfunction "GND_E9") (pintype "power_in"))
      (node (ref "U1") (pin "F10") (pinfunction "GND_F10") (pintype "power_in"))
      (node (ref "U1") (pin "F16") (pinfunction "GND_F16") (pintype "power_in"))
      (node (ref "U1") (pin "F6") (pinfunction "GND_F6") (pintype "power_in"))
      (node (ref "U1") (pin "F8") (pinfunction "VCCBATT_0_F8") (pintype "power_in"))
      (node (ref "U1") (pin "G13") (pinfunction "GND_G13") (pintype "power_in"))
      (node (ref "U1") (pin "G3") (pinfunction "GND_G3") (pintype "power_in"))
      (node (ref "U1") (pin "G9") (pinfunction "GND_G9") (pintype "power_in"))
      (node (ref "U1") (pin "H6") (pinfunction "GND_H6") (pintype "power_in"))
      (node (ref "U1") (pin "J11") (pinfunction "GND_J11") (pintype "power_in"))
      (node (ref "U1") (pin "J9") (pinfunction "GND_J9") (pintype "power_in"))
      (node (ref "U1") (pin "K14") (pinfunction "GND_K14") (pintype "power_in"))
      (node (ref "U1") (pin "K4") (pinfunction "GND_K4") (pintype "power_in"))
      (node (ref "U1") (pin "K6") (pinfunction "GND_K6") (pintype "power_in"))
      (node (ref "U1") (pin "K7") (pinfunction "DXN_0_K7") (pintype "input"))
      (node (ref "U1") (pin "K8") (pinfunction "DXP_0_K8") (pintype "input"))
      (node (ref "U1") (pin "L1") (pinfunction "GND_L1") (pintype "power_in"))
      (node (ref "U1") (pin "L11") (pinfunction "GND_L11") (pintype "power_in"))
      (node (ref "U1") (pin "M8") (pinfunction "GND_M8") (pintype "power_in"))
      (node (ref "U1") (pin "N15") (pinfunction "GND_N15") (pintype "power_in"))
      (node (ref "U1") (pin "N5") (pinfunction "GND_N5") (pintype "power_in"))
      (node (ref "U1") (pin "P12") (pinfunction "GND_P12") (pintype "power_in"))
      (node (ref "U1") (pin "P2") (pinfunction "GND_P2") (pintype "power_in"))
      (node (ref "U1") (pin "R9") (pinfunction "GND_R9") (pintype "power_in"))
      (node (ref "U1") (pin "T16") (pinfunction "GND_T16") (pintype "power_in"))
      (node (ref "U1") (pin "T6") (pinfunction "GND_T6") (pintype "power_in"))
    )
    (net (code "21") (name "Net-(D6-C)") (class "Default")
      (node (ref "D6") (pin "1") (pinfunction "C_1") (pintype "passive"))
      (node (ref "R10") (pin "1") (pinfunction "1_1") (pintype "passive"))
    )
    (net (code "22") (name "Net-(U1G-VCCADC_0)") (class "Default")
      (node (ref "C1") (pin "1") (pinfunction "1_1") (pintype "passive"))
      (node (ref "C18") (pin "2") (pinfunction "2_2") (pintype "passive"))
      (node (ref "FB3") (pin "1") (pinfunction "1_1") (pintype "passive"))
      (node (ref "U1") (pin "G8") (pinfunction "VCCADC_0_G8") (pintype "power_in"))
    )
    (net (code "23") (name "unconnected-(U1C-IO_0_34-PadL5)") (class "Default")
      (node (ref "U1") (pin "L5") (pinfunction "IO_0_34_L5") (pintype "bidirectional"))
    )
    (net (code "24") (name "unconnected-(U1C-IO_L1N_T0_34-PadM4)") (class "Default")
      (node (ref "U1") (pin "M4") (pinfunction "IO_L1N_T0_34_M4") (pintype "bidirectional"))
    )
    (net (code "25") (name "unconnected-(U1C-IO_L1P_T0_34-PadL4)") (class "Default")
      (node (ref "U1") (pin "L4") (pinfunction "IO_L1P_T0_34_L4") (pintype "bidirectional"))
    )
    (net (code "26") (name "unconnected-(U1C-IO_L2N_T0_34-PadM1)") (class "Default")
      (node (ref "U1") (pin "M1") (pinfunction "IO_L2N_T0_34_M1") (pintype "bidirectional"))
    )
    (net (code "27") (name "unconnected-(U1C-IO_L2P_T0_34-PadM2)") (class "Default")
      (node (ref "U1") (pin "M2") (pinfunction "IO_L2P_T0_34_M2") (pintype "bidirectional"))
    )
    (net (code "28") (name "unconnected-(U1C-IO_L3N_T0_DQS_34-PadN2)") (class "Default")
      (node (ref "U1") (pin "N2") (pinfunction "IO_L3N_T0_DQS_34_N2") (pintype "bidirectional"))
    )
    (net (code "29") (name "unconnected-(U1C-IO_L3P_T0_DQS_34-PadN3)") (class "Default")
      (node (ref "U1") (pin "N3") (pinfunction "IO_L3P_T0_DQS_34_N3") (pintype "bidirectional"))
    )
    (net (code "30") (name "unconnected-(U1C-IO_L4N_T0_34-PadP1)") (class "Default")
      (node (ref "U1") (pin "P1") (pinfunction "IO_L4N_T0_34_P1") (pintype "bidirectional"))
    )
    (net (code "31") (name "unconnected-(U1C-IO_L4P_T0_34-PadN1)") (class "Default")
      (node (ref "U1") (pin "N1") (pinfunction "IO_L4P_T0_34_N1") (pintype "bidirectional"))
    )
    (net (code "32") (name "unconnected-(U1C-IO_L5N_T0_34-PadP3)") (class "Default")
      (node (ref "U1") (pin "P3") (pinfunction "IO_L5N_T0_34_P3") (pintype "bidirectional"))
    )
    (net (code "33") (name "unconnected-(U1C-IO_L5P_T0_34-PadP4)") (class "Default")
      (node (ref "U1") (pin "P4") (pinfunction "IO_L5P_T0_34_P4") (pintype "bidirectional"))
    )
    (net (code "34") (name "unconnected-(U1C-IO_L6N_T0_VREF_34-PadN4)") (class "Default")
      (node (ref "U1") (pin "N4") (pinfunction "IO_L6N_T0_VREF_34_N4") (pintype "bidirectional"))
    )
    (net (code "35") (name "unconnected-(U1C-IO_L6P_T0_34-PadM5)") (class "Default")
      (node (ref "U1") (pin "M5") (pinfunction "IO_L6P_T0_34_M5") (pintype "bidirectional"))
    )
    (net (code "36") (name "unconnected-(U1C-IO_L7N_T1_34-PadR1)") (class "Default")
      (node (ref "U1") (pin "R1") (pinfunction "IO_L7N_T1_34_R1") (pintype "bidirectional"))
    )
    (net (code "37") (name "unconnected-(U1C-IO_L7P_T1_34-PadR2)") (class "Default")
      (node (ref "U1") (pin "R2") (pinfunction "IO_L7P_T1_34_R2") (pintype "bidirectional"))
    )
    (net (code "38") (name "unconnected-(U1C-IO_L8N_T1_34-PadT2)") (class "Default")
      (node (ref "U1") (pin "T2") (pinfunction "IO_L8N_T1_34_T2") (pintype "bidirectional"))
    )
    (net (code "39") (name "unconnected-(U1C-IO_L8P_T1_34-PadR3)") (class "Default")
      (node (ref "U1") (pin "R3") (pinfunction "IO_L8P_T1_34_R3") (pintype "bidirectional"))
    )
    (net (code "40") (name "unconnected-(U1C-IO_L9N_T1_DQS_34-PadT3)") (class "Default")
      (node (ref "U1") (pin "T3") (pinfunction "IO_L9N_T1_DQS_34_T3") (pintype "bidirectional"))
    )
    (net (code "41") (name "unconnected-(U1C-IO_L9P_T1_DQS_34-PadT4)") (class "Default")
      (node (ref "U1") (pin "T4") (pinfunction "IO_L9P_T1_DQS_34_T4") (pintype "bidirectional"))
    )
    (net (code "42") (name "unconnected-(U1C-IO_L10P_T1_34-PadP5)") (class "Default")
      (node (ref "U1") (pin "P5") (pinfunction "IO_L10P_T1_34_P5") (pintype "bidirectional"))
    )
  )
)
